# TIDA-010967_USB_PWR_Connector.net
KiCad netlist of a schematic drawn in Altium Designer
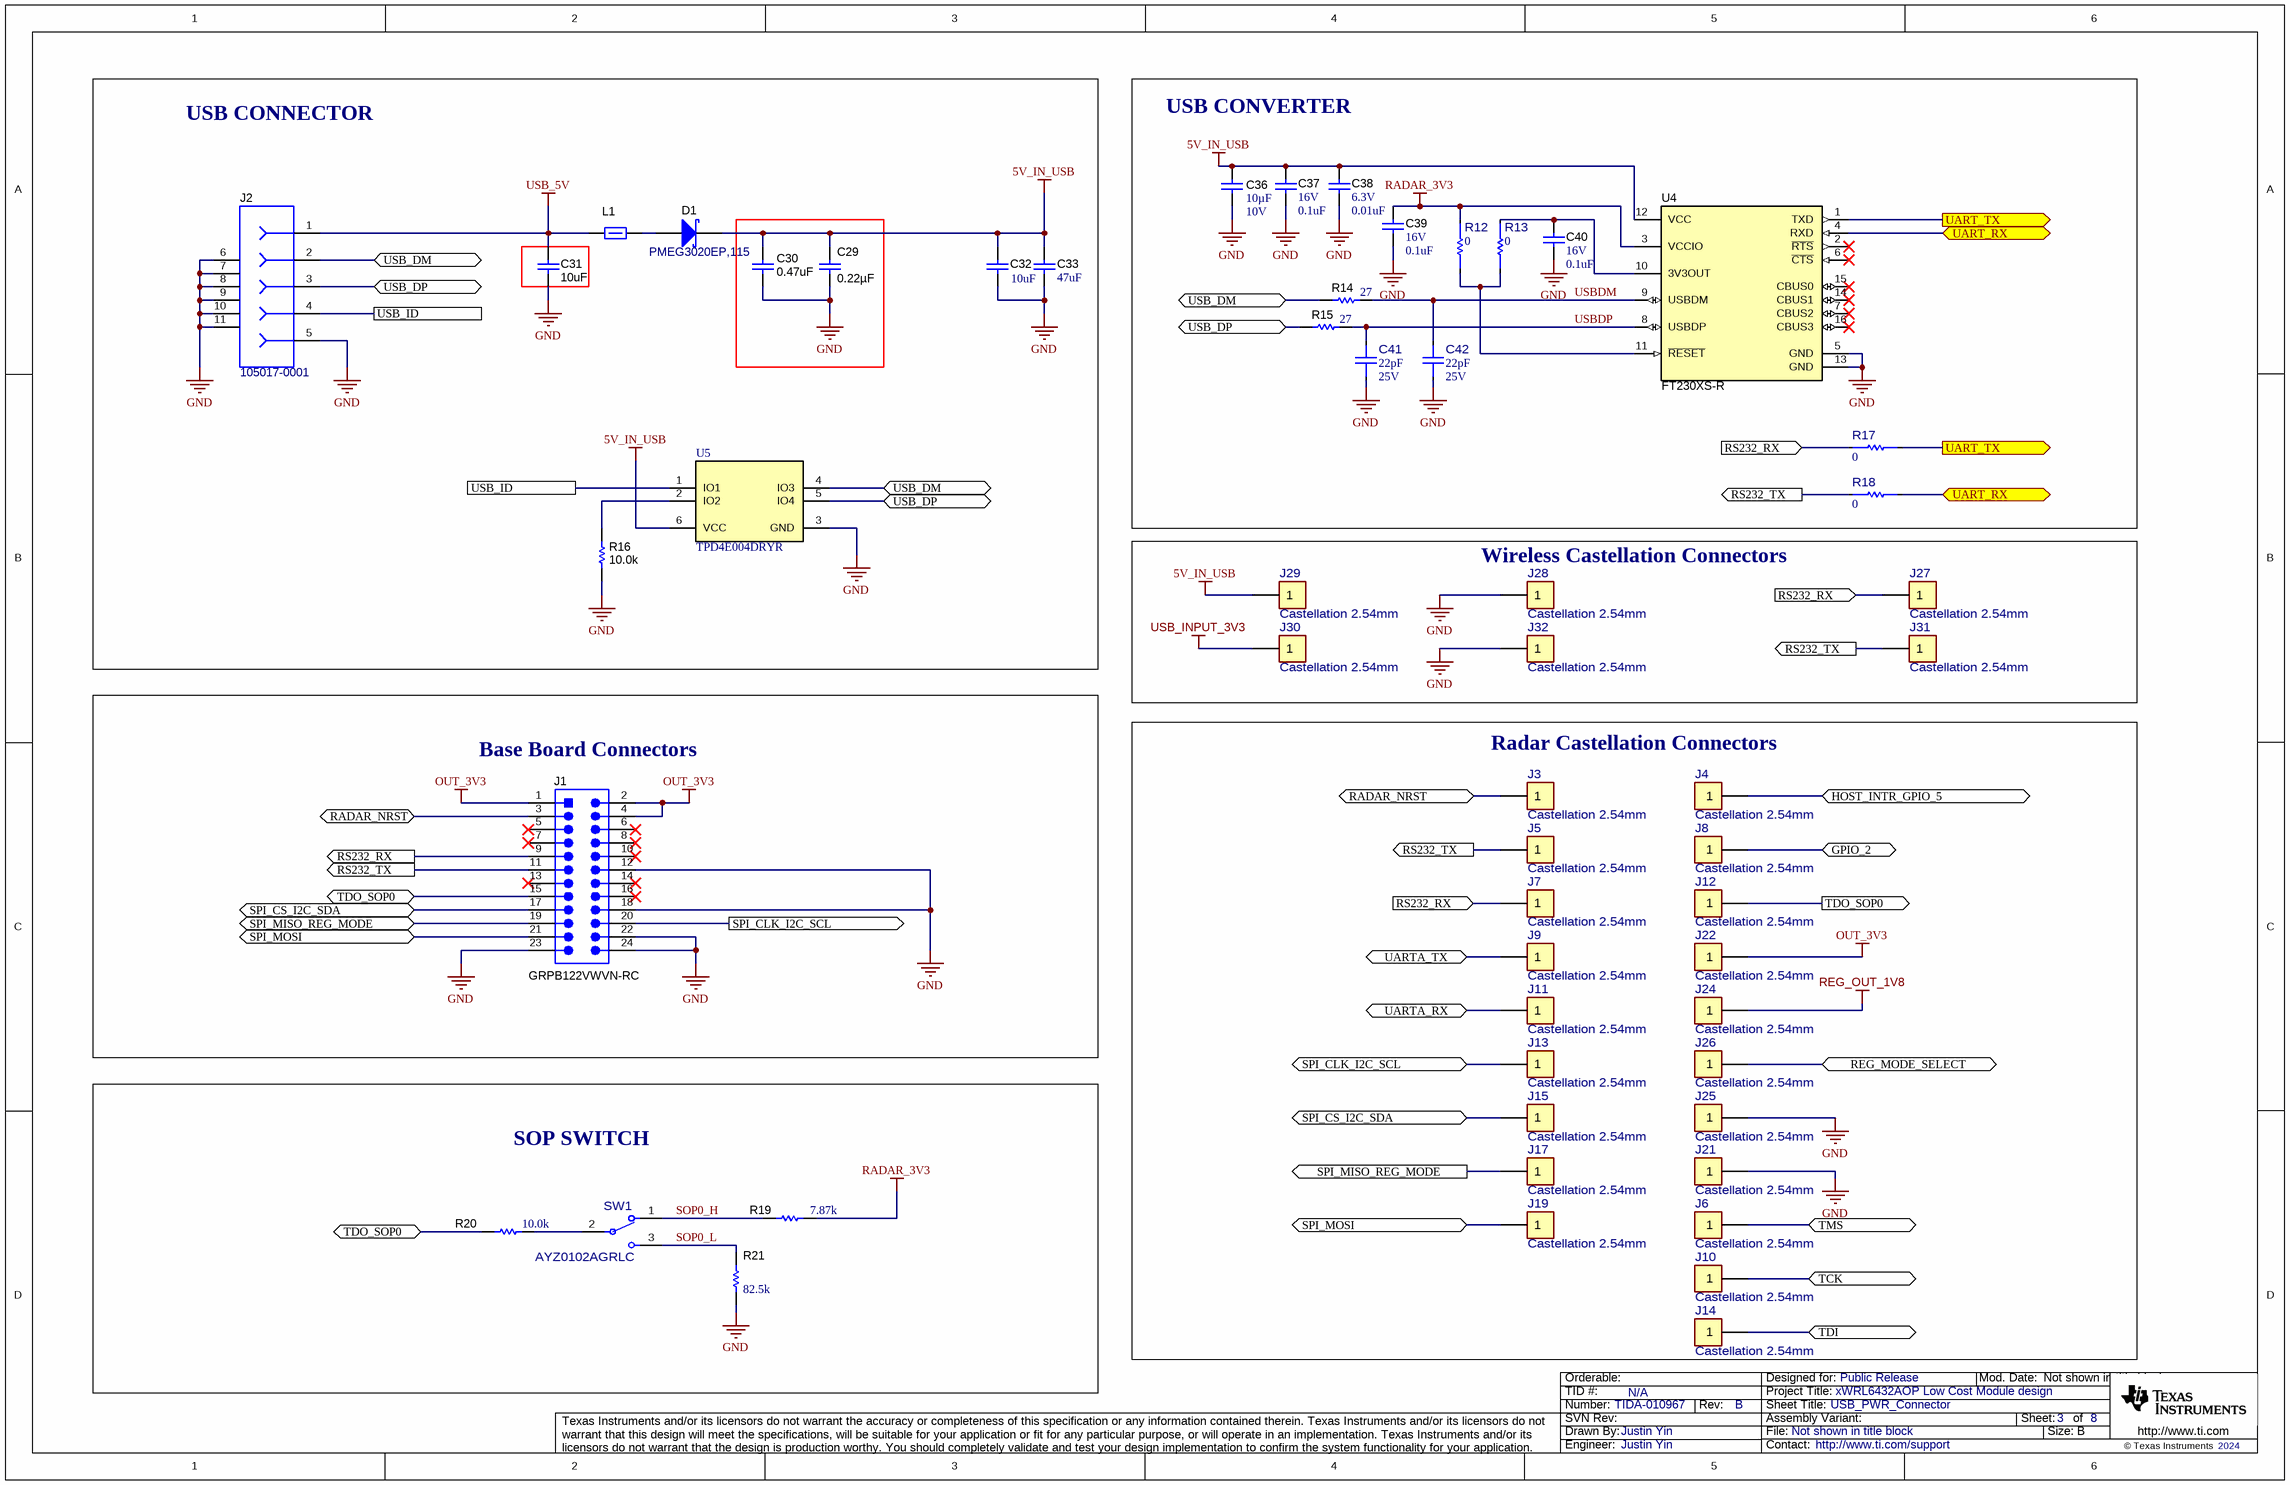
[diagram p0: TIDA-010967_USB_PWR_Connector.SchDoc]

(export (version "E")
  (design (tool "Eeschema 10.0.6"))
  (components
    (comp (ref "C29")
      (value "GCM155R71C224KE02D")
      (footprint "0402L")
      (description "CAP, CERM, 0.22 µF, 16 V,+/- 10%, X7R, AEC-Q200 Grade 1, 0402")
      (fields (field (name "MANUFACTURER") "MuRata") (field (name "VALUEDISPLAYED") "0.22µF"))
      (libsource (lib "Altium Vault - TI") (part "CMP-0078265-1"))
    )
    (comp (ref "C30")
      (value "GCM155C71A474KE36D")
      (footprint "0402L")
      (description "CAP, CERM, 0.47 uF, 10 V,+/- 10%, X7S, 0402")
      (fields
        (field (name "VALUEDISPLAYED") "0.47uF")
        (field (name "MANUFACTURER") "MuRata")
        (field (name "PUBLISHER") "Texas Instruments")
      )
      (libsource (lib "Altium Vault - TI") (part "Capacitor"))
    )
    (comp (ref "C31")
      (value "GRT188R61A106KE13D")
      (footprint "0603S")
      (description "CAP, CERM, 10 uF, 10 V, +/- 10%, X5R, 0603")
      (fields
        (field (name "VALUEDISPLAYED") "10uF")
        (field (name "MANUFACTURER") "MuRata")
        (field (name "PUBLISHER") "Texas Instruments")
      )
      (libsource (lib "Altium Vault - TI") (part "Capacitor"))
    )
    (comp (ref "C32")
      (value "GRM155R61A106ME11D")
      (footprint "0402")
      (description "CAP, CERM, 10 uF, 10 V, +/- 20%, X5R, 0402")
      (fields
        (field (name "MANUFACTURER") "MuRata")
        (field (name "VALUEDISPLAYED") "10uF")
        (field (name "PUBLISHER") "Texas Instruments")
      )
      (libsource (lib "Altium Vault - TI") (part "Capacitor"))
    )
    (comp (ref "C33")
      (value "GRM31CR61A476KE15L")
      (footprint "1206_180")
      (description "CAP, CERM, 47 uF, 10 V, +/- 10%, X5R, 1206")
      (fields
        (field (name "MANUFACTURER") "MuRata")
        (field (name "VALUEDISPLAYED") "47uF")
        (field (name "PUBLISHER") "Texas Instruments")
      )
      (libsource (lib "Altium Vault - TI") (part "Capacitor"))
    )
    (comp (ref "C36")
      (value "0402ZD106MAT2A")
      (footprint "0402_080")
      (description "CAP, CERM, 10 µF, 10 V,+/- 20%, X5R, 0402")
      (fields
        (field (name "MANUFACTURER") "AVX")
        (field (name "VDC_V") "10V")
        (field (name "VALUEDISPLAYED") "10µF")
      )
      (libsource (lib "Altium Vault - TI") (part "Capacitor"))
    )
    (comp (ref "C37")
      (value "GRM033R61C104KE84D")
      (footprint "0201_033")
      (description "CAP, CERM, 0.1 uF, 16 V, +/- 10%, X5R, 0201")
      (fields
        (field (name "MANUFACTURER") "MuRata")
        (field (name "VDC_V") "16V")
        (field (name "VALUEDISPLAYED") "0.1uF")
        (field (name "PUBLISHER") "Texas Instruments")
      )
      (libsource (lib "Altium Vault - TI") (part "Capacitor"))
    )
    (comp (ref "C38")
      (value "GRM033R70J103KA01D")
      (footprint "0201")
      (description "CAP, CERM, 0.01 uF, 6.3 V, +/- 10%, X7R, 0201")
      (fields
        (field (name "MANUFACTURER") "MuRata")
        (field (name "VDC_V") "6.3V")
        (field (name "VALUEDISPLAYED") "0.01uF")
        (field (name "PUBLISHER") "Texas Instruments")
      )
      (libsource (lib "Altium Vault - TI") (part "Capacitor"))
    )
    (comp (ref "C39")
      (value "GRM033R61C104KE84D")
      (footprint "0201_033")
      (description "CAP, CERM, 0.1 uF, 16 V, +/- 10%, X5R, 0201")
      (fields
        (field (name "MANUFACTURER") "MuRata")
        (field (name "VDC_V") "16V")
        (field (name "VALUEDISPLAYED") "0.1uF")
        (field (name "PUBLISHER") "Texas Instruments")
      )
      (libsource (lib "Altium Vault - TI") (part "Capacitor"))
    )
    (comp (ref "C40")
      (value "GRM033R61C104KE84D")
      (footprint "0201_033")
      (description "CAP, CERM, 0.1 uF, 16 V, +/- 10%, X5R, 0201")
      (fields
        (field (name "MANUFACTURER") "MuRata")
        (field (name "VDC_V") "16V")
        (field (name "VALUEDISPLAYED") "0.1uF")
        (field (name "PUBLISHER") "Texas Instruments")
      )
      (libsource (lib "Altium Vault - TI") (part "Capacitor"))
    )
    (comp (ref "C41")
      (value "GCM0335C1E220JA16D")
      (footprint "FP-GCM0335C1E220JA16D_0201-MFG")
      (description "Ceramic Capacitor for Automotive 22pF  ±5% 25VDC C0G 0201 Paper T/R")
      (fields
        (field (name "MANUFACTURER") "Murata")
        (field (name "VALUEDISPLAYED") "22pF")
        (field (name "VDC_V") "25V")
      )
      (libsource (lib "Altium Vault - TI") (part "SYM-GCM0335C1E220JA16D"))
    )
    (comp (ref "C42")
      (value "GCM0335C1E220JA16D")
      (footprint "FP-GCM0335C1E220JA16D_0201-MFG")
      (description "Ceramic Capacitor for Automotive 22pF  ±5% 25VDC C0G 0201 Paper T/R")
      (fields
        (field (name "MANUFACTURER") "Murata")
        (field (name "VALUEDISPLAYED") "22pF")
        (field (name "VDC_V") "25V")
      )
      (libsource (lib "Altium Vault - TI") (part "SYM-GCM0335C1E220JA16D"))
    )
    (comp (ref "D1")
      (value "PMEG3020EP,115")
      (footprint "SOD-128")
      (description "Diode, Schottky, 30 V, 2 A, AEC-Q101, SOD-128")
      (fields (field (name "MANUFACTURER") "Nexperia"))
      (libsource (lib "Altium Vault - TI") (part "DIODE_SCHOTTKY"))
    )
    (comp (ref "J1")
      (value "GRPB122VWVN-RC")
      (footprint "Sullins_GRPB122VWVN")
      (description "Header, 1.27mm, 12x2, Gold, TH")
      (fields
        (field (name "MANUFACTURER") "Sullins Connector Solutions")
        (field (name "PUBLISHER") "Texas Instruments")
      )
      (libsource (lib "Altium Vault - TI") (part "Header_12x2"))
    )
    (comp (ref "J2")
      (value "105017-0001")
      (footprint "CONN_105017-0001")
      (description "Connector, Receptacle, Micro-USB Type B, R/A, Bottom Mount SMT")
      (fields (field (name "MANUFACTURER") "Molex") (field (name "PUBLISHER") "Texas Instruments"))
      (libsource (lib "Altium Vault - TI") (part "CONN_105017-0001"))
    )
    (comp (ref "J3")
      (value "Castellation 2.54mm")
      (footprint "FP-Castellation 2.54mm_75mills")
      (fields (field (name "MANUFACTURER") "Altium"))
      (libsource (lib "Altium Vault - TI") (part "SYM-Castellation 2.54mm"))
    )
    (comp (ref "J4")
      (value "Castellation 2.54mm")
      (footprint "FP-Castellation 2.54mm_75mills")
      (fields (field (name "MANUFACTURER") "Altium"))
      (libsource (lib "") (part "SYM-Castellation 2.54mm_1"))
    )
    (comp (ref "J5")
      (value "Castellation 2.54mm")
      (footprint "FP-Castellation 2.54mm_75mills")
      (fields (field (name "MANUFACTURER") "Altium"))
      (libsource (lib "Altium Vault - TI") (part "SYM-Castellation 2.54mm"))
    )
    (comp (ref "J6")
      (value "Castellation 2.54mm")
      (footprint "FP-Castellation 2.54mm_75mills")
      (fields (field (name "MANUFACTURER") "Altium"))
      (libsource (lib "") (part "SYM-Castellation 2.54mm_2"))
    )
    (comp (ref "J7")
      (value "Castellation 2.54mm")
      (footprint "FP-Castellation 2.54mm_75mills")
      (fields (field (name "MANUFACTURER") "Altium"))
      (libsource (lib "Altium Vault - TI") (part "SYM-Castellation 2.54mm"))
    )
    (comp (ref "J8")
      (value "Castellation 2.54mm")
      (footprint "FP-Castellation 2.54mm_75mills")
      (fields (field (name "MANUFACTURER") "Altium"))
      (libsource (lib "") (part "SYM-Castellation 2.54mm_1"))
    )
    (comp (ref "J9")
      (value "Castellation 2.54mm")
      (footprint "FP-Castellation 2.54mm_75mills")
      (fields (field (name "MANUFACTURER") "Altium"))
      (libsource (lib "Altium Vault - TI") (part "SYM-Castellation 2.54mm"))
    )
    (comp (ref "J10")
      (value "Castellation 2.54mm")
      (footprint "FP-Castellation 2.54mm_75mills")
      (fields (field (name "MANUFACTURER") "Altium"))
      (libsource (lib "") (part "SYM-Castellation 2.54mm_2"))
    )
    (comp (ref "J11")
      (value "Castellation 2.54mm")
      (footprint "FP-Castellation 2.54mm_75mills")
      (fields (field (name "MANUFACTURER") "Altium"))
      (libsource (lib "Altium Vault - TI") (part "SYM-Castellation 2.54mm"))
    )
    (comp (ref "J12")
      (value "Castellation 2.54mm")
      (footprint "FP-Castellation 2.54mm_75mills")
      (fields (field (name "MANUFACTURER") "Altium"))
      (libsource (lib "") (part "SYM-Castellation 2.54mm_1"))
    )
    (comp (ref "J13")
      (value "Castellation 2.54mm")
      (footprint "FP-Castellation 2.54mm_75mills")
      (fields (field (name "MANUFACTURER") "Altium"))
      (libsource (lib "Altium Vault - TI") (part "SYM-Castellation 2.54mm"))
    )
    (comp (ref "J14")
      (value "Castellation 2.54mm")
      (footprint "FP-Castellation 2.54mm_75mills")
      (fields (field (name "MANUFACTURER") "Altium"))
      (libsource (lib "") (part "SYM-Castellation 2.54mm_2"))
    )
    (comp (ref "J15")
      (value "Castellation 2.54mm")
      (footprint "FP-Castellation 2.54mm_75mills")
      (fields (field (name "MANUFACTURER") "Altium"))
      (libsource (lib "Altium Vault - TI") (part "SYM-Castellation 2.54mm"))
    )
    (comp (ref "J17")
      (value "Castellation 2.54mm")
      (footprint "FP-Castellation 2.54mm_75mills")
      (fields (field (name "MANUFACTURER") "Altium"))
      (libsource (lib "Altium Vault - TI") (part "SYM-Castellation 2.54mm"))
    )
    (comp (ref "J19")
      (value "Castellation 2.54mm")
      (footprint "FP-Castellation 2.54mm_75mills")
      (fields (field (name "MANUFACTURER") "Altium"))
      (libsource (lib "Altium Vault - TI") (part "SYM-Castellation 2.54mm"))
    )
    (comp (ref "J21")
      (value "Castellation 2.54mm")
      (footprint "FP-Castellation 2.54mm_75mills")
      (fields (field (name "MANUFACTURER") "Altium"))
      (libsource (lib "") (part "SYM-Castellation 2.54mm_2"))
    )
    (comp (ref "J22")
      (value "Castellation 2.54mm")
      (footprint "FP-Castellation 2.54mm_75mills")
      (fields (field (name "MANUFACTURER") "Altium"))
      (libsource (lib "") (part "SYM-Castellation 2.54mm_1"))
    )
    (comp (ref "J24")
      (value "Castellation 2.54mm")
      (footprint "FP-Castellation 2.54mm_75mills")
      (fields (field (name "MANUFACTURER") "Altium"))
      (libsource (lib "") (part "SYM-Castellation 2.54mm_1"))
    )
    (comp (ref "J25")
      (value "Castellation 2.54mm")
      (footprint "FP-Castellation 2.54mm_75mills")
      (fields (field (name "MANUFACTURER") "Altium"))
      (libsource (lib "") (part "SYM-Castellation 2.54mm_2"))
    )
    (comp (ref "J26")
      (value "Castellation 2.54mm")
      (footprint "FP-Castellation 2.54mm_75mills")
      (fields (field (name "MANUFACTURER") "Altium"))
      (libsource (lib "") (part "SYM-Castellation 2.54mm_1"))
    )
    (comp (ref "J27")
      (value "Castellation 2.54mm")
      (footprint "FP-Castellation 2.54mm_75mills")
      (fields (field (name "MANUFACTURER") "Altium"))
      (libsource (lib "Altium Vault - TI") (part "SYM-Castellation 2.54mm"))
    )
    (comp (ref "J28")
      (value "Castellation 2.54mm")
      (footprint "FP-Castellation 2.54mm_75mills")
      (fields (field (name "MANUFACTURER") "Altium"))
      (libsource (lib "Altium Vault - TI") (part "SYM-Castellation 2.54mm"))
    )
    (comp (ref "J29")
      (value "Castellation 2.54mm")
      (footprint "FP-Castellation 2.54mm_75mills")
      (fields (field (name "MANUFACTURER") "Altium"))
      (libsource (lib "Altium Vault - TI") (part "SYM-Castellation 2.54mm"))
    )
    (comp (ref "J30")
      (value "Castellation 2.54mm")
      (footprint "FP-Castellation 2.54mm_75mills")
      (fields (field (name "MANUFACTURER") "Altium"))
      (libsource (lib "Altium Vault - TI") (part "SYM-Castellation 2.54mm"))
    )
    (comp (ref "J31")
      (value "Castellation 2.54mm")
      (footprint "FP-Castellation 2.54mm_75mills")
      (fields (field (name "MANUFACTURER") "Altium"))
      (libsource (lib "Altium Vault - TI") (part "SYM-Castellation 2.54mm"))
    )
    (comp (ref "J32")
      (value "Castellation 2.54mm")
      (footprint "FP-Castellation 2.54mm_75mills")
      (fields (field (name "MANUFACTURER") "Altium"))
      (libsource (lib "Altium Vault - TI") (part "SYM-Castellation 2.54mm"))
    )
    (comp (ref "L1")
      (value "BLM15PD300SZ1D")
      (footprint "0402L")
      (description "Inductor, Ferrite Bead, Ferrite, 2.2 A, 0.035 ohm, AEC-Q200 Grade 1, SMD")
      (fields (field (name "MANUFACTURER") "MuRata") (field (name "PUBLISHER") "Texas Instruments"))
      (libsource (lib "Altium Vault - TI") (part "Ferrite_Bead"))
    )
    (comp (ref "R12")
      (value "0")
      (footprint "FP-RC0402JR-070RP_0402-MFG")
      (description "Res Jumper Thick Film 0402 0 Ohm 5% 1/16W Molded SMD Paper T/R")
      (fields (field (name "MOUSER PART NUMBER") "603-RC0402JR-070RP") (field (name "MANUFACTURER") "Yageo"))
      (libsource (lib "Altium Vault - TI") (part "SYM-RC0402JR-070RP"))
    )
    (comp (ref "R13")
      (value "0")
      (footprint "FP-RC0402JR-070RP_0402-MFG")
      (description "Res Jumper Thick Film 0402 0 Ohm 5% 1/16W Molded SMD Paper T/R")
      (fields (field (name "MOUSER PART NUMBER") "603-RC0402JR-070RP") (field (name "MANUFACTURER") "Yageo"))
      (libsource (lib "Altium Vault - TI") (part "SYM-RC0402JR-070RP"))
    )
    (comp (ref "R14")
      (value "RC0201JR-0727RL")
      (footprint "0201")
      (description "RES, 27, 5%, 0.05 W, 0201")
      (fields
        (field (name "MANUFACTURER") "Yageo America")
        (field (name "VALUEDISPLAYED") "27")
        (field (name "PUBLISHER") "Texas Instruments")
      )
      (libsource (lib "Altium Vault - TI") (part "Resistor"))
    )
    (comp (ref "R15")
      (value "RC0201JR-0727RL")
      (footprint "0201")
      (description "RES, 27, 5%, 0.05 W, 0201")
      (fields
        (field (name "MANUFACTURER") "Yageo America")
        (field (name "VALUEDISPLAYED") "27")
        (field (name "PUBLISHER") "Texas Instruments")
      )
      (libsource (lib "Altium Vault - TI") (part "Resistor"))
    )
    (comp (ref "R16")
      (value "CRCW040210K0FKED")
      (footprint "0402L")
      (description "RES, 10.0 k, 1%, 0.063 W, AEC-Q200 Grade 0, 0402")
      (fields (field (name "MANUFACTURER") "Vishay-Dale") (field (name "VALUEDISPLAYED") "10.0k"))
      (libsource (lib "Altium Vault - TI") (part "Resistor"))
    )
    (comp (ref "R17")
      (value "0")
      (footprint "FP-RC0402JR-070RP_0402-MFG")
      (description "Res Jumper Thick Film 0402 0 Ohm 5% 1/16W Molded SMD Paper T/R")
      (fields (field (name "MOUSER PART NUMBER") "603-RC0402JR-070RP") (field (name "MANUFACTURER") "Yageo"))
      (libsource (lib "Altium Vault - TI") (part "SYM-RC0402JR-070RP"))
    )
    (comp (ref "R18")
      (value "0")
      (footprint "FP-RC0402JR-070RP_0402-MFG")
      (description "Res Jumper Thick Film 0402 0 Ohm 5% 1/16W Molded SMD Paper T/R")
      (fields (field (name "MOUSER PART NUMBER") "603-RC0402JR-070RP") (field (name "MANUFACTURER") "Yageo"))
      (libsource (lib "Altium Vault - TI") (part "SYM-RC0402JR-070RP"))
    )
    (comp (ref "R19")
      (value "CRCW04027K87FKED")
      (footprint "0402L")
      (description "RES, 7.87 k, 1%, 0.063 W, AEC-Q200 Grade 0, 0402")
      (fields (field (name "MANUFACTURER") "Vishay-Dale") (field (name "VALUEDISPLAYED") "7.87k"))
      (libsource (lib "Altium Vault - TI") (part "Resistor"))
    )
    (comp (ref "R20")
      (value "CRCW040210K0FKED")
      (footprint "0402L")
      (description "RES, 10.0 k, 1%, 0.063 W, AEC-Q200 Grade 0, 0402")
      (fields (field (name "MANUFACTURER") "Vishay-Dale") (field (name "VALUEDISPLAYED") "10.0k"))
      (libsource (lib "Altium Vault - TI") (part "Resistor"))
    )
    (comp (ref "R21")
      (value "CRCW040282K5FKED")
      (footprint "0402L")
      (description "RES, 82.5 k, 1%, 0.063 W, AEC-Q200 Grade 0, 0402")
      (fields (field (name "MANUFACTURER") "Vishay-Dale") (field (name "VALUEDISPLAYED") "82.5k"))
      (libsource (lib "Altium Vault - TI") (part "Resistor"))
    )
    (comp (ref "SW1")
      (value "AYZ0102AGRLC")
      (footprint "FP-AYZ0102AGRLC_SMT_SW_7MM2_5MM3-MFG")
      (description "Slide Switch SPDT Surface Mount, Right Angle")
      (fields
        (field (name "MOUSER PART NUMBER") "611-AYZ0102AGRLC")
        (field (name "DIGIKEY PART NUMBER") "401-2012-1-ND")
      )
      (libsource (lib "Altium Vault - TI") (part "SYM-AYZ0102AGRLC"))
    )
    (comp (ref "U4")
      (value "FT230XS-R")
      (footprint "SSOP-16")
      (description "USB to UART, SSOP-16")
      (fields (field (name "MANUFACTURER") "FTDI") (field (name "PUBLISHER") "Texas Instruments"))
      (libsource (lib "Altium Vault - TI") (part "FT230XS"))
    )
    (comp (ref "U5")
      (value "TPD4E004DRYR")
      (footprint "DRY0006A")
      (description "4-Channel ESD Protection Array for High-Speed Data Interfaces, DRY0006A (USON-6)")
      (fields (field (name "MANUFACTURER") "Texas Instruments") (field (name "PARTNUMBER") "TPD4E004DRYR"))
      (libsource (lib "Altium Vault - TI") (part "TI-TPD4E004-SON_DRY-6"))
    )
  )
  (nets
    (net (code "1") (name "/GPIO_2") (class "Default")
      (node (ref "J8") (pin "1") (pinfunction "1_1") (pintype "passive"))
    )
    (net (code "2") (name "/HOST_INTR_GPIO_5") (class "Default")
      (node (ref "J4") (pin "1") (pinfunction "1_1") (pintype "passive"))
    )
    (net (code "3") (name "/RADAR_NRST") (class "Default")
      (node (ref "J1") (pin "3") (pinfunction "3_3") (pintype "passive"))
      (node (ref "J3") (pin "1") (pinfunction "1_1") (pintype "passive"))
    )
    (net (code "4") (name "/REG_MODE_SELECT") (class "Default")
      (node (ref "J26") (pin "1") (pinfunction "1_1") (pintype "passive"))
    )
    (net (code "5") (name "/RS232_RX") (class "Default")
      (node (ref "J1") (pin "9") (pinfunction "9_9") (pintype "passive"))
      (node (ref "J27") (pin "1") (pinfunction "1_1") (pintype "passive"))
      (node (ref "J7") (pin "1") (pinfunction "1_1") (pintype "passive"))
      (node (ref "R17") (pin "1") (pinfunction "1_1") (pintype "passive"))
    )
    (net (code "6") (name "/RS232_TX") (class "Default")
      (node (ref "J1") (pin "11") (pinfunction "11_11") (pintype "passive"))
      (node (ref "J31") (pin "1") (pinfunction "1_1") (pintype "passive"))
      (node (ref "J5") (pin "1") (pinfunction "1_1") (pintype "passive"))
      (node (ref "R18") (pin "1") (pinfunction "1_1") (pintype "passive"))
    )
    (net (code "7") (name "/SOP0_H") (class "Default")
      (node (ref "R19") (pin "1") (pinfunction "1_1") (pintype "passive"))
      (node (ref "SW1") (pin "1") (pinfunction "1_1") (pintype "passive"))
    )
    (net (code "8") (name "/SOP0_L") (class "Default")
      (node (ref "R21") (pin "2") (pinfunction "2_2") (pintype "passive"))
      (node (ref "SW1") (pin "3") (pinfunction "3_3") (pintype "passive"))
    )
    (net (code "9") (name "/SPI_CLK_I2C_SCL") (class "Default")
      (node (ref "J1") (pin "20") (pinfunction "20_20") (pintype "passive"))
      (node (ref "J13") (pin "1") (pinfunction "1_1") (pintype "passive"))
    )
    (net (code "10") (name "/SPI_CS_I2C_SDA") (class "Default")
      (node (ref "J1") (pin "17") (pinfunction "17_17") (pintype "passive"))
      (node (ref "J15") (pin "1") (pinfunction "1_1") (pintype "passive"))
    )
    (net (code "11") (name "/SPI_MISO_REG_MODE") (class "Default")
      (node (ref "J1") (pin "19") (pinfunction "19_19") (pintype "passive"))
      (node (ref "J17") (pin "1") (pinfunction "1_1") (pintype "passive"))
    )
    (net (code "12") (name "/SPI_MOSI") (class "Default")
      (node (ref "J1") (pin "21") (pinfunction "21_21") (pintype "passive"))
      (node (ref "J19") (pin "1") (pinfunction "1_1") (pintype "passive"))
    )
    (net (code "13") (name "/TCK") (class "Default")
      (node (ref "J10") (pin "1") (pinfunction "1_1") (pintype "passive"))
    )
    (net (code "14") (name "/TDI") (class "Default")
      (node (ref "J14") (pin "1") (pinfunction "1_1") (pintype "passive"))
    )
    (net (code "15") (name "/TDO_SOP0") (class "Default")
      (node (ref "J1") (pin "15") (pinfunction "15_15") (pintype "passive"))
      (node (ref "J12") (pin "1") (pinfunction "1_1") (pintype "passive"))
      (node (ref "R20") (pin "1") (pinfunction "1_1") (pintype "passive"))
    )
    (net (code "16") (name "/TMS") (class "Default")
      (node (ref "J6") (pin "1") (pinfunction "1_1") (pintype "passive"))
    )
    (net (code "17") (name "/UARTA_RX") (class "Default")
      (node (ref "J11") (pin "1") (pinfunction "1_1") (pintype "passive"))
    )
    (net (code "18") (name "/UARTA_TX") (class "Default")
      (node (ref "J9") (pin "1") (pinfunction "1_1") (pintype "passive"))
    )
    (net (code "19") (name "/UART_RX") (class "Default")
      (node (ref "R18") (pin "2") (pinfunction "2_2") (pintype "passive"))
      (node (ref "U4") (pin "4") (pinfunction "RXD_4") (pintype "input"))
    )
    (net (code "20") (name "/UART_TX") (class "Default")
      (node (ref "R17") (pin "2") (pinfunction "2_2") (pintype "passive"))
      (node (ref "U4") (pin "1") (pinfunction "TXD_1") (pintype "output"))
    )
    (net (code "21") (name "/USBDM") (class "Default")
      (node (ref "C42") (pin "2") (pinfunction "2_2") (pintype "passive"))
      (node (ref "R14") (pin "2") (pinfunction "2_2") (pintype "passive"))
      (node (ref "U4") (pin "9") (pinfunction "USBDM_9") (pintype "bidirectional"))
    )
    (net (code "22") (name "/USBDP") (class "Default")
      (node (ref "C41") (pin "2") (pinfunction "2_2") (pintype "passive"))
      (node (ref "R15") (pin "2") (pinfunction "2_2") (pintype "passive"))
      (node (ref "U4") (pin "8") (pinfunction "USBDP_8") (pintype "bidirectional"))
    )
    (net (code "23") (name "/USB_DM") (class "Default")
      (node (ref "J2") (pin "2") (pintype "passive"))
      (node (ref "R14") (pin "1") (pinfunction "1_1") (pintype "passive"))
      (node (ref "U5") (pin "4") (pinfunction "IO3_4") (pintype "passive"))
    )
    (net (code "24") (name "/USB_DP") (class "Default")
      (node (ref "J2") (pin "3") (pintype "passive"))
      (node (ref "R15") (pin "1") (pinfunction "1_1") (pintype "passive"))
      (node (ref "U5") (pin "5") (pinfunction "IO4_5") (pintype "passive"))
    )
    (net (code "25") (name "/USB_ID") (class "Default")
      (node (ref "J2") (pin "4") (pintype "passive"))
      (node (ref "U5") (pin "1") (pinfunction "IO1_1") (pintype "passive"))
    )
    (net (code "26") (name "5V_IN_USB") (class "Default")
      (node (ref "C29") (pin "2") (pinfunction "2_2") (pintype "passive"))
      (node (ref "C30") (pin "1") (pinfunction "1_1") (pintype "passive"))
      (node (ref "C32") (pin "2") (pinfunction "2_2") (pintype "passive"))
      (node (ref "C33") (pin "1") (pinfunction "1_1") (pintype "passive"))
      (node (ref "C36") (pin "1") (pinfunction "1_1") (pintype "passive"))
      (node (ref "C37") (pin "1") (pinfunction "1_1") (pintype "passive"))
      (node (ref "C38") (pin "1") (pinfunction "1_1") (pintype "passive"))
      (node (ref "D1") (pin "1") (pinfunction "K_1") (pintype "passive"))
      (node (ref "J29") (pin "1") (pinfunction "1_1") (pintype "passive"))
      (node (ref "U4") (pin "12") (pinfunction "VCC_12") (pintype "power_in"))
      (node (ref "U5") (pin "6") (pinfunction "VCC_6") (pintype "power_in"))
    )
    (net (code "27") (name "GND") (class "Default")
      (node (ref "C29") (pin "1") (pinfunction "1_1") (pintype "passive"))
      (node (ref "C30") (pin "2") (pinfunction "2_2") (pintype "passive"))
      (node (ref "C31") (pin "1") (pinfunction "1_1") (pintype "passive"))
      (node (ref "C32") (pin "1") (pinfunction "1_1") (pintype "passive"))
      (node (ref "C33") (pin "2") (pinfunction "2_2") (pintype "passive"))
      (node (ref "C36") (pin "2") (pinfunction "2_2") (pintype "passive"))
      (node (ref "C37") (pin "2") (pinfunction "2_2") (pintype "passive"))
      (node (ref "C38") (pin "2") (pinfunction "2_2") (pintype "passive"))
      (node (ref "C39") (pin "2") (pinfunction "2_2") (pintype "passive"))
      (node (ref "C40") (pin "2") (pinfunction "2_2") (pintype "passive"))
      (node (ref "C41") (pin "1") (pinfunction "1_1") (pintype "passive"))
      (node (ref "C42") (pin "1") (pinfunction "1_1") (pintype "passive"))
      (node (ref "J1") (pin "12") (pinfunction "12_12") (pintype "passive"))
      (node (ref "J1") (pin "18") (pinfunction "18_18") (pintype "passive"))
      (node (ref "J1") (pin "22") (pinfunction "22_22") (pintype "passive"))
      (node (ref "J1") (pin "23") (pinfunction "23_23") (pintype "passive"))
      (node (ref "J1") (pin "24") (pinfunction "24_24") (pintype "passive"))
      (node (ref "J2") (pin "10") (pintype "passive"))
      (node (ref "J2") (pin "11") (pintype "passive"))
      (node (ref "J2") (pin "5") (pintype "passive"))
      (node (ref "J2") (pin "6") (pintype "passive"))
      (node (ref "J2") (pin "7") (pintype "passive"))
      (node (ref "J2") (pin "8") (pintype "passive"))
      (node (ref "J2") (pin "9") (pintype "passive"))
      (node (ref "J21") (pin "1") (pinfunction "1_1") (pintype "passive"))
      (node (ref "J25") (pin "1") (pinfunction "1_1") (pintype "passive"))
      (node (ref "J28") (pin "1") (pinfunction "1_1") (pintype "passive"))
      (node (ref "J32") (pin "1") (pinfunction "1_1") (pintype "passive"))
      (node (ref "R16") (pin "1") (pinfunction "1_1") (pintype "passive"))
      (node (ref "R21") (pin "1") (pinfunction "1_1") (pintype "passive"))
      (node (ref "U4") (pin "13") (pinfunction "GND_13") (pintype "power_in"))
      (node (ref "U4") (pin "5") (pinfunction "GND_5") (pintype "power_in"))
      (node (ref "U5") (pin "3") (pinfunction "GND_3") (pintype "power_in"))
    )
    (net (code "28") (name "Net-(D1-A)") (class "Default")
      (node (ref "D1") (pin "2") (pinfunction "A_2") (pintype "passive"))
      (node (ref "L1") (pin "2") (pinfunction "2_2") (pintype "passive"))
    )
    (net (code "29") (name "Net-(SW1-C)") (class "Default")
      (node (ref "R20") (pin "2") (pinfunction "2_2") (pintype "passive"))
      (node (ref "SW1") (pin "2") (pinfunction "C_2") (pintype "passive"))
    )
    (net (code "30") (name "Net-(U4-3V3OUT)") (class "Default")
      (node (ref "C40") (pin "1") (pinfunction "1_1") (pintype "passive"))
      (node (ref "R13") (pin "1") (pinfunction "1_1") (pintype "passive"))
      (node (ref "U4") (pin "10") (pinfunction "3V3OUT_10") (pintype "power_in"))
    )
    (net (code "31") (name "Net-(U4-RESET)") (class "Default")
      (node (ref "R12") (pin "2") (pinfunction "2_2") (pintype "passive"))
      (node (ref "R13") (pin "2") (pinfunction "2_2") (pintype "passive"))
      (node (ref "U4") (pin "11") (pinfunction "RESET_11") (pintype "input"))
    )
    (net (code "32") (name "Net-(U5-IO2)") (class "Default")
      (node (ref "R16") (pin "2") (pinfunction "2_2") (pintype "passive"))
      (node (ref "U5") (pin "2") (pinfunction "IO2_2") (pintype "passive"))
    )
    (net (code "33") (name "OUT_3V3") (class "Default")
      (node (ref "J1") (pin "1") (pinfunction "1_1") (pintype "passive"))
      (node (ref "J1") (pin "2") (pinfunction "2_2") (pintype "passive"))
      (node (ref "J1") (pin "4") (pinfunction "4_4") (pintype "passive"))
      (node (ref "J22") (pin "1") (pinfunction "1_1") (pintype "passive"))
    )
    (net (code "34") (name "RADAR_3V3") (class "Default")
      (node (ref "C39") (pin "1") (pinfunction "1_1") (pintype "passive"))
      (node (ref "R12") (pin "1") (pinfunction "1_1") (pintype "passive"))
      (node (ref "R19") (pin "2") (pinfunction "2_2") (pintype "passive"))
      (node (ref "U4") (pin "3") (pinfunction "VCCIO_3") (pintype "power_in"))
    )
    (net (code "35") (name "REG_OUT_1V8") (class "Default")
      (node (ref "J24") (pin "1") (pinfunction "1_1") (pintype "passive"))
    )
    (net (code "36") (name "USB_5V") (class "Default")
      (node (ref "C31") (pin "2") (pinfunction "2_2") (pintype "passive"))
      (node (ref "J2") (pin "1") (pintype "passive"))
      (node (ref "L1") (pin "1") (pinfunction "1_1") (pintype "passive"))
    )
    (net (code "37") (name "USB_INPUT_3V3") (class "Default")
      (node (ref "J30") (pin "1") (pinfunction "1_1") (pintype "passive"))
    )
    (net (code "38") (name "unconnected-(J1-Pad5)") (class "Default")
      (node (ref "J1") (pin "5") (pinfunction "5_5") (pintype "passive+no_connect"))
    )
    (net (code "39") (name "unconnected-(J1-Pad6)") (class "Default")
      (node (ref "J1") (pin "6") (pinfunction "6_6") (pintype "passive+no_connect"))
    )
    (net (code "40") (name "unconnected-(J1-Pad7)") (class "Default")
      (node (ref "J1") (pin "7") (pinfunction "7_7") (pintype "passive+no_connect"))
    )
    (net (code "41") (name "unconnected-(J1-Pad8)") (class "Default")
      (node (ref "J1") (pin "8") (pinfunction "8_8") (pintype "passive+no_connect"))
    )
    (net (code "42") (name "unconnected-(J1-Pad10)") (class "Default")
      (node (ref "J1") (pin "10") (pinfunction "10_10") (pintype "passive+no_connect"))
    )
    (net (code "43") (name "unconnected-(J1-Pad13)") (class "Default")
      (node (ref "J1") (pin "13") (pinfunction "13_13") (pintype "passive+no_connect"))
    )
    (net (code "44") (name "unconnected-(J1-Pad14)") (class "Default")
      (node (ref "J1") (pin "14") (pinfunction "14_14") (pintype "passive+no_connect"))
    )
    (net (code "45") (name "unconnected-(J1-Pad16)") (class "Default")
      (node (ref "J1") (pin "16") (pinfunction "16_16") (pintype "passive+no_connect"))
    )
    (net (code "46") (name "unconnected-(U4-CBUS0-Pad15)") (class "Default")
      (node (ref "U4") (pin "15") (pinfunction "CBUS0_15") (pintype "bidirectional+no_connect"))
    )
    (net (code "47") (name "unconnected-(U4-CBUS1-Pad14)") (class "Default")
      (node (ref "U4") (pin "14") (pinfunction "CBUS1_14") (pintype "bidirectional+no_connect"))
    )
    (net (code "48") (name "unconnected-(U4-CBUS2-Pad7)") (class "Default")
      (node (ref "U4") (pin "7") (pinfunction "CBUS2_7") (pintype "bidirectional+no_connect"))
    )
    (net (code "49") (name "unconnected-(U4-CBUS3-Pad16)") (class "Default")
      (node (ref "U4") (pin "16") (pinfunction "CBUS3_16") (pintype "bidirectional+no_connect"))
    )
    (net (code "50") (name "unconnected-(U4-CTS-Pad6)") (class "Default")
      (node (ref "U4") (pin "6") (pinfunction "CTS_6") (pintype "input+no_connect"))
    )
    (net (code "51") (name "unconnected-(U4-RTS-Pad2)") (class "Default")
      (node (ref "U4") (pin "2") (pinfunction "RTS_2") (pintype "output+no_connect"))
    )
  )
)
